# LCDTFT_FPC40P_RGB_FULL.net
KiCad netlist of a schematic drawn in Altium Designer
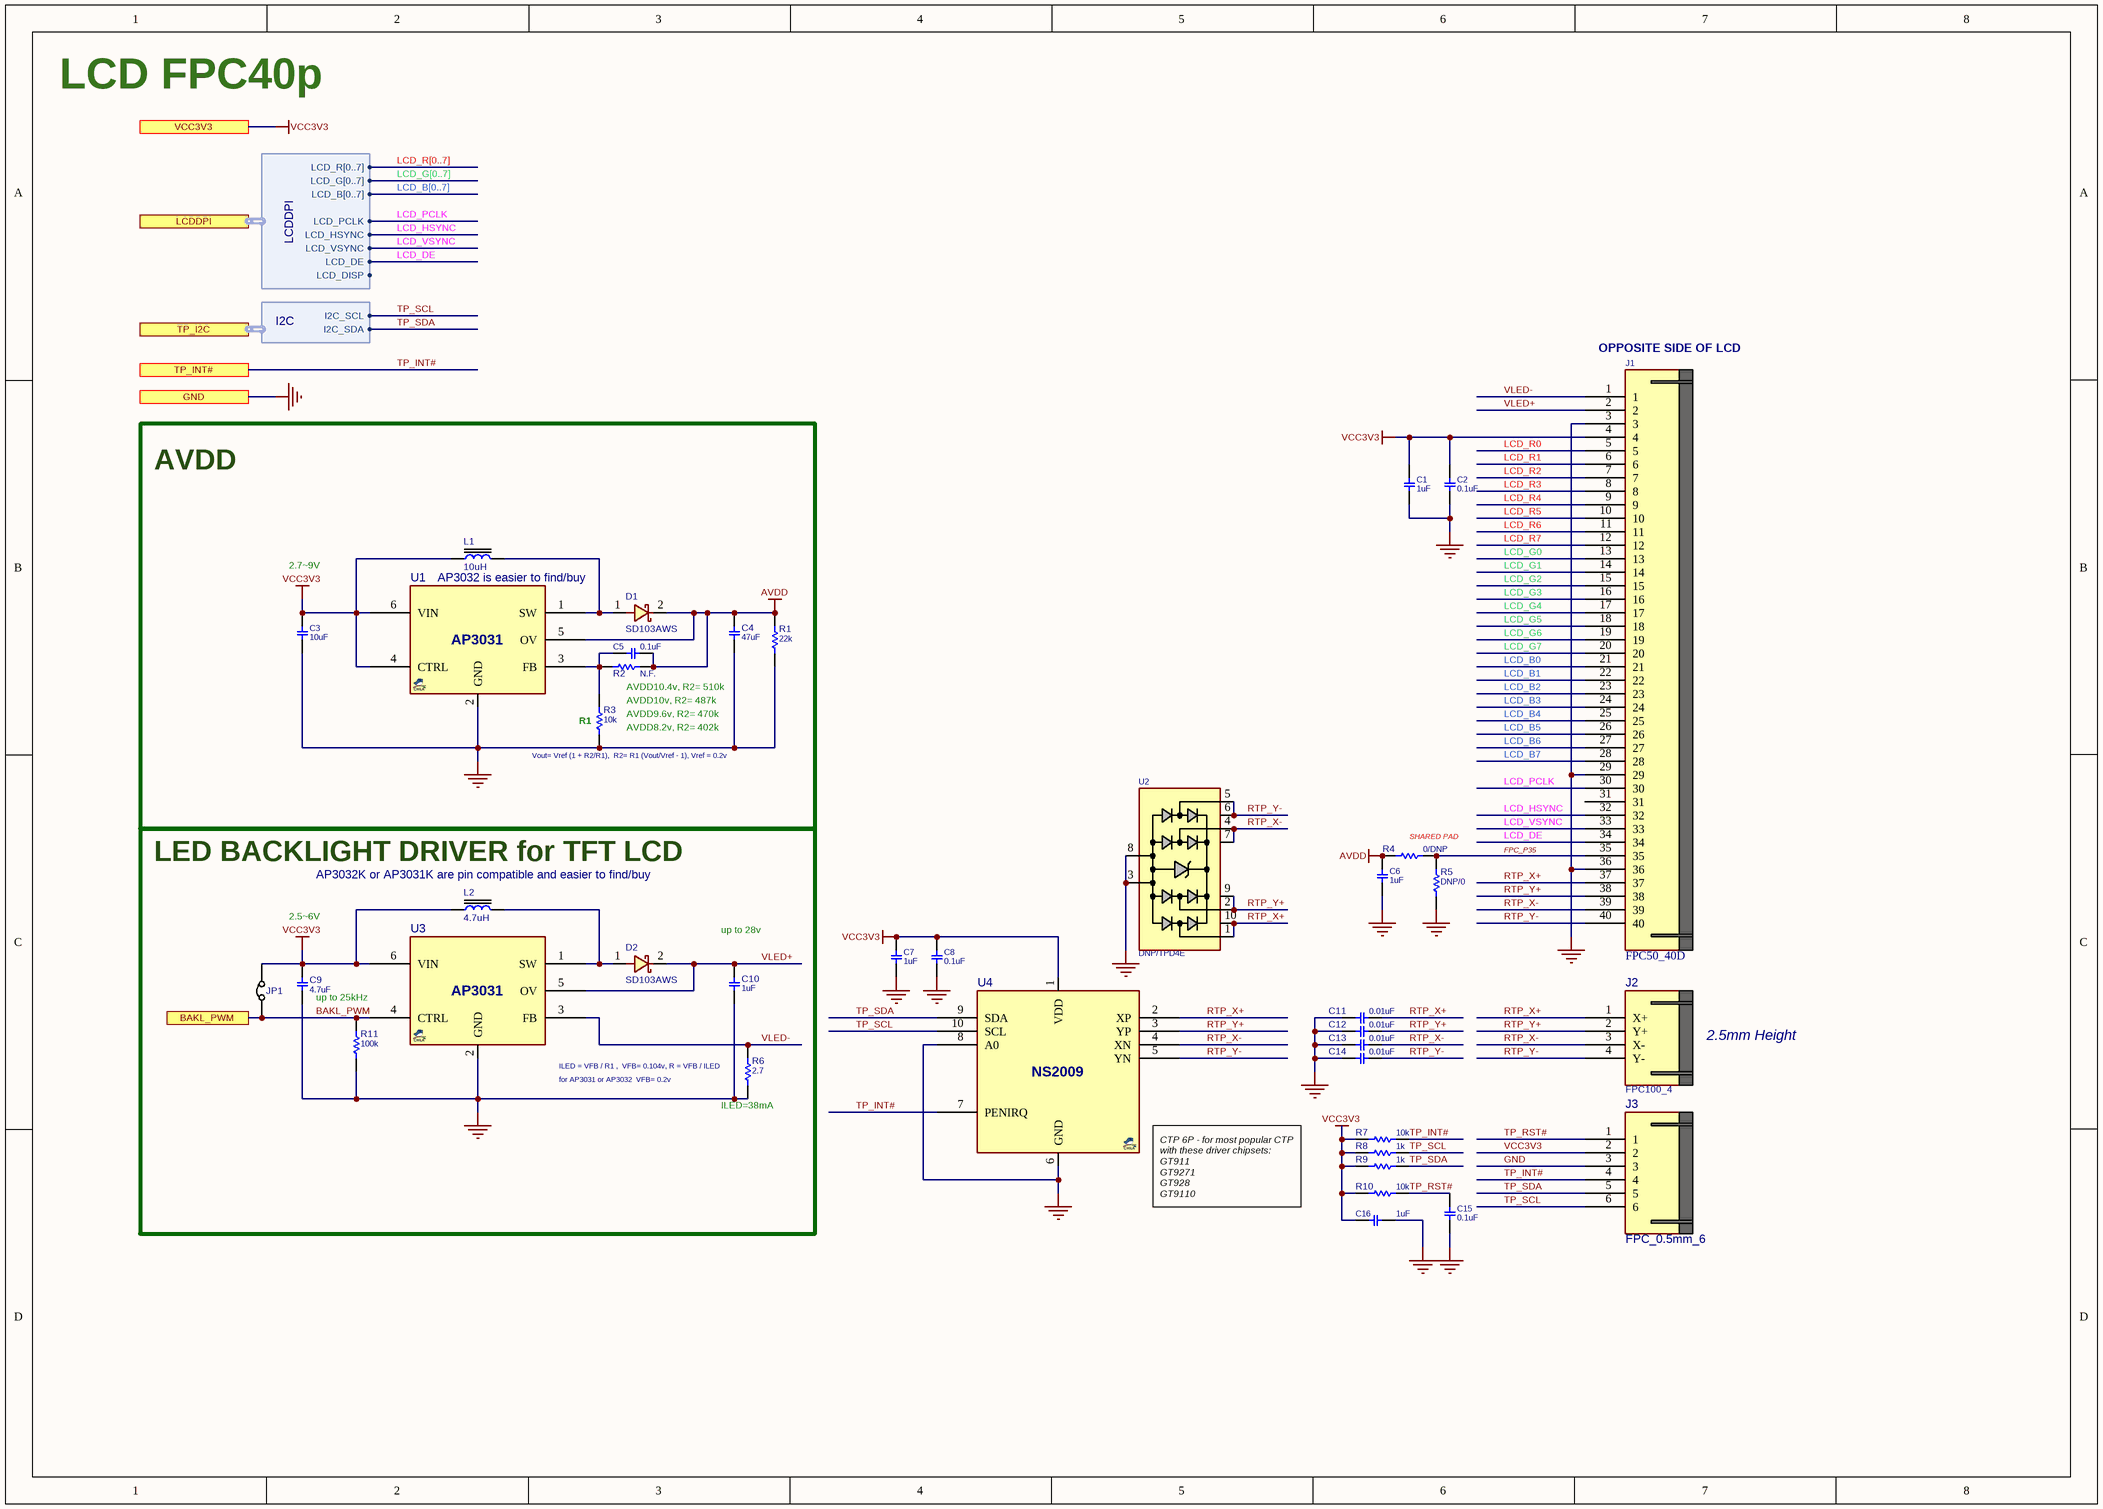
[diagram p0: LCDTFT_FPC40P_RGB_FULL.SchDoc]

(export (version "E")
  (design (tool "Eeschema 10.0.6"))
  (components
    (comp (ref "C1")
      (value "1uF")
      (footprint "C0402")
      (description "CAP, MLCC")
      (fields (field (name "MANF_P#") "CL05A105KO5NNND") (field (name "MANF") "Samsung"))
      (libsource (lib "passive_smd") (part "CAP_SMD_MLCC"))
    )
    (comp (ref "C2")
      (value "0.1uF")
      (footprint "C0402")
      (description "CAP, MLCC")
      (fields (field (name "MANF_P#") "GRM155R71H104KE14D") (field (name "MANF") "Murata"))
      (libsource (lib "passive_smd") (part "CAP_SMD_MLCC"))
    )
    (comp (ref "C3")
      (value "10uF")
      (footprint "C0402")
      (description "CAP, MLCC")
      (fields (field (name "MANF_P#") "CL05A106MP5NUNC") (field (name "MANF") "Samsung"))
      (libsource (lib "passive_smd") (part "CAP_SMD_MLCC"))
    )
    (comp (ref "C4")
      (value "47uF")
      (footprint "C1206")
      (description "CAP, MLCC")
      (fields (field (name "MANF_P#") "GRM31CR61E476ME44L") (field (name "MANF") "Murata"))
      (libsource (lib "passive_smd") (part "CAP_SMD_MLCC"))
    )
    (comp (ref "C5")
      (value "0.1uF")
      (footprint "C0402")
      (description "CAP, MLCC, 100nF, 50V, X7R, 10%, 0402C")
      (fields (field (name "MANF") "Murata") (field (name "MANF_P#") "GCM155R71H104KE02D"))
      (libsource (lib "passive_mlcc_smd") (part "CAP_SMD_MLCC_100n50V"))
    )
    (comp (ref "C6")
      (value "1uF")
      (footprint "C0402")
      (description "CAP, MLCC")
      (fields (field (name "MANF_P#") "CL05A105KO5NNND") (field (name "MANF") "Samsung"))
      (libsource (lib "passive_smd") (part "CAP_SMD_MLCC"))
    )
    (comp (ref "C7")
      (value "1uF")
      (footprint "C0402")
      (description "CAP, MLCC")
      (fields (field (name "MANF_P#") "GMK105ABJ105KV-F") (field (name "MANF") "Taiyo Yuden"))
      (libsource (lib "passive_smd") (part "CAP_SMD_MLCC"))
    )
    (comp (ref "C8")
      (value "0.1uF")
      (footprint "C0402")
      (description "CAP, MLCC")
      (fields (field (name "MANF_P#") "GRM155R71H104KE14D") (field (name "MANF") "Murata"))
      (libsource (lib "passive_smd") (part "CAP_SMD_MLCC"))
    )
    (comp (ref "C9")
      (value "4.7uF")
      (footprint "C0402")
      (description "CAP, MLCC")
      (fields (field (name "MANF_P#") "LMK105BBJ475MVLF") (field (name "MANF") "Taiyo Yuden"))
      (libsource (lib "passive_smd") (part "CAP_SMD_MLCC"))
    )
    (comp (ref "C10")
      (value "1uF")
      (footprint "C0603")
      (description "CAP, MLCC")
      (fields (field (name "MANF_P#") "CL10A105KB8NNNC") (field (name "MANF") "Samsung"))
      (libsource (lib "passive_smd") (part "CAP_SMD_MLCC"))
    )
    (comp (ref "C11")
      (value "0.01uF")
      (footprint "C0402")
      (description "CAP, MLCC")
      (libsource (lib "passive_smd") (part "CAP_SMD_MLCC"))
    )
    (comp (ref "C12")
      (value "0.01uF")
      (footprint "C0402")
      (description "CAP, MLCC")
      (libsource (lib "passive_smd") (part "CAP_SMD_MLCC"))
    )
    (comp (ref "C13")
      (value "0.01uF")
      (footprint "C0402")
      (description "CAP, MLCC")
      (libsource (lib "passive_smd") (part "CAP_SMD_MLCC"))
    )
    (comp (ref "C14")
      (value "0.01uF")
      (footprint "C0402")
      (description "CAP, MLCC")
      (libsource (lib "passive_smd") (part "CAP_SMD_MLCC"))
    )
    (comp (ref "C15")
      (value "0.1uF")
      (footprint "C0402")
      (description "CAP, MLCC")
      (fields (field (name "MANF_P#") "GRM155R71H104KE14D") (field (name "MANF") "Murata"))
      (libsource (lib "passive_smd") (part "CAP_SMD_MLCC"))
    )
    (comp (ref "C16")
      (value "1uF")
      (footprint "C0402")
      (description "CAP, MLCC")
      (fields (field (name "MANF_P#") "CL05A105KO5NNND") (field (name "MANF") "Samsung"))
      (libsource (lib "passive_smd") (part "CAP_SMD_MLCC"))
    )
    (comp (ref "D1")
      (value "SD103AWS")
      (footprint "D_SOD323")
      (description "DIODE, SCHOTTKY, 40V, 2A")
      (fields (field (name "MANF") "DIODES"))
      (libsource (lib "diode") (part "DIODE_SMD_SCHOTTKY_1N5819"))
    )
    (comp (ref "D2")
      (value "SD103AWS")
      (footprint "D_SOD323")
      (description "DIODE, SCHOTTKY, 40V, 2A")
      (fields (field (name "MANF") "DIODES"))
      (libsource (lib "diode") (part "DIODE_SMD_SCHOTTKY_1N5819"))
    )
    (comp (ref "J1")
      (value "FPC50_40D")
      (footprint "FPC50_40D_FFC2B29")
      (description "CONN, FPC, 0.50mm pitch, RightAngle, Dual side Contact")
      (fields (field (name "MANF") "GCT") (field (name "MANF_P#") "FFC2B29-40-G"))
      (libsource (lib "conn_fpc") (part "FPC50_40D_FFC2B29"))
    )
    (comp (ref "J2")
      (value "FPC100_4")
      (footprint "FPC100_4HT")
      (description "LCD Resistive touch, FPC 4pin")
      (libsource (lib "lcdtft") (part "LCD_RTP_FPC4P"))
    )
    (comp (ref "J3")
      (value "FPC_0.5mm_6")
      (footprint "FPC50_6")
      (description "CONN, FPC, 0.50mm pitch, RightAngle, Bot. Contact, Hinge type")
      (fields (field (name "MANF") "FCI") (field (name "MANF_P#") "SFV6R1STBE1HLF"))
      (libsource (lib "conn_fpc") (part "FPC50_6"))
    )
    (comp (ref "JP1")
      (value "JMPSOLDER")
      (footprint "JP_60X100")
      (description "JUMPER, HEADER 2PIN")
      (fields (field (name "MANF") "MANF") (field (name "MANF_P#") "MANF_P#"))
      (libsource (lib "test-tp_jumper") (part "JUMPER_SOLDER"))
    )
    (comp (ref "L1")
      (value "10uH")
      (footprint "L_4")
      (description "INDUCTOR, POWER, SMD")
      (fields (field (name "MANF_P#") "GCD43-100MC"))
      (libsource (lib "passive") (part "INDPWR_SMD"))
    )
    (comp (ref "L2")
      (value "4.7uH")
      (footprint "L1008")
      (description "INDUCTOR, POWER, SMD")
      (fields (field (name "MANF_P#") "TMS252012ALM-4R7MTAA"))
      (libsource (lib "passive") (part "INDPWR_SMD"))
    )
    (comp (ref "R1")
      (value "22k")
      (footprint "R0402")
      (description "RESISTOR, SMD, 20K, 0402")
      (fields (field (name "MANF") "Yageo") (field (name "MANF_P#") "RK73H1ETTP2002F"))
      (libsource (lib "chila_passive") (part "RES_SMD"))
    )
    (comp (ref "R2")
      (value "N.F.")
      (footprint "R0402")
      (description "RESISTOR, SMD, 20K, 0402")
      (fields (field (name "MANF") "Yageo") (field (name "MANF_P#") "RK73H1ETTP2002F"))
      (libsource (lib "chila_passive") (part "RES_SMD"))
    )
    (comp (ref "R3")
      (value "10k")
      (footprint "R0402")
      (description "RESISTOR, SMD, 20K, 0402")
      (fields (field (name "MANF") "Yageo") (field (name "MANF_P#") "RK73H1ETTP2002F"))
      (libsource (lib "chila_passive") (part "RES_SMD"))
    )
    (comp (ref "R4")
      (value "0/DNP")
      (footprint "R0402")
      (description "RESISTOR, SMD")
      (libsource (lib "passive_res_smd") (part "RES_SMD"))
    )
    (comp (ref "R5")
      (value "DNP/0")
      (footprint "R0402")
      (description "RESISTOR, SMD")
      (libsource (lib "passive_res_smd") (part "RES_SMD"))
    )
    (comp (ref "R6")
      (value "2.7")
      (footprint "R0402")
      (description "RESISTOR, SMD, 20K, 0402")
      (fields (field (name "MANF") "Yageo") (field (name "MANF_P#") "RK73H1ETTP2002F"))
      (libsource (lib "chila_passive") (part "RES_SMD"))
    )
    (comp (ref "R7")
      (value "10k")
      (footprint "R0402")
      (description "RESISTOR, SMD")
      (libsource (lib "passive_res_smd") (part "RES_SMD"))
    )
    (comp (ref "R8")
      (value "1k")
      (footprint "R0402")
      (description "RESISTOR, SMD")
      (libsource (lib "passive_res_smd") (part "RES_SMD"))
    )
    (comp (ref "R9")
      (value "1k")
      (footprint "R0402")
      (description "RESISTOR, SMD")
      (libsource (lib "passive_res_smd") (part "RES_SMD"))
    )
    (comp (ref "R10")
      (value "10k")
      (footprint "R0402")
      (description "RESISTOR, SMD")
      (libsource (lib "passive_res_smd") (part "RES_SMD"))
    )
    (comp (ref "R11")
      (value "100k")
      (footprint "R0402")
      (description "RESISTOR, SMD, 20K, 0402")
      (fields (field (name "MANF") "Yageo") (field (name "MANF_P#") "RK73H1ETTP2002F"))
      (libsource (lib "chila_passive") (part "RES_SMD"))
    )
    (comp (ref "U1")
      (value "AP3031")
      (footprint "SOT23_6")
      (description "REG, Switching, Boost, 1.4A, ADJ, 1MHz, SOT-23-6")
      (fields (field (name "MANF_P#") "AP3031K") (field (name "MANF") "Diodes"))
      (libsource (lib "pwr_switching_boost") (part "VREG_AP3031_SOT23"))
    )
    (comp (ref "U2")
      (value "DNP/TPD4E")
      (footprint "SON50_10_2510E")
      (description "TVS, ESD PROTECT, 4CH,")
      (fields (field (name "MANF_P#") "TPD4E05U06DQA") (field (name "MANF") "Texas Instruments"))
      (libsource (lib "protect_tvs_esd_fuse") (part "TVS_X4_TPD4E05U06"))
    )
    (comp (ref "U3")
      (value "AP3031")
      (footprint "SOT23_6")
      (description "REG, Switching, Boost, 1.4A, ADJ, 1MHz, SOT-23-6")
      (fields (field (name "MANF_P#") "AP3031K") (field (name "MANF") "Diodes"))
      (libsource (lib "pwr_switching_boost") (part "VREG_AP3031_SOT23"))
    )
    (comp (ref "U4")
      (value "NS2009")
      (footprint "SOG50_10")
      (description "LCD, Touch Screen Controller, 12Bit, I2C, MSOP-10")
      (fields (field (name "MANF") "NSWAY"))
      (libsource (lib "lcd_resistive_touch_driver") (part "NS2009_MSOP10"))
    )
  )
  (nets
    (net (code "3") (name "/BAKL_PWM") (class "Default")
      (node (ref "JP1") (pin "1") (pinfunction "1_1") (pintype "passive"))
      (node (ref "R11") (pin "1") (pinfunction "1_1") (pintype "passive"))
      (node (ref "U3") (pin "4") (pinfunction "CTRL_4") (pintype "passive"))
    )
    (net (code "4") (name "/FPC_P35") (class "Default")
      (node (ref "J1") (pin "35") (pinfunction "35_35") (pintype "passive"))
      (node (ref "R4") (pin "2") (pinfunction "2_2") (pintype "passive"))
      (node (ref "R5") (pin "1") (pinfunction "1_1") (pintype "passive"))
    )
    (net (code "6") (name "/LCD_B0") (class "Default")
      (node (ref "J1") (pin "21") (pinfunction "21_21") (pintype "passive"))
    )
    (net (code "7") (name "/LCD_B1") (class "Default")
      (node (ref "J1") (pin "22") (pinfunction "22_22") (pintype "passive"))
    )
    (net (code "8") (name "/LCD_B2") (class "Default")
      (node (ref "J1") (pin "23") (pinfunction "23_23") (pintype "passive"))
    )
    (net (code "9") (name "/LCD_B3") (class "Default")
      (node (ref "J1") (pin "24") (pinfunction "24_24") (pintype "passive"))
    )
    (net (code "10") (name "/LCD_B4") (class "Default")
      (node (ref "J1") (pin "25") (pinfunction "25_25") (pintype "passive"))
    )
    (net (code "11") (name "/LCD_B5") (class "Default")
      (node (ref "J1") (pin "26") (pinfunction "26_26") (pintype "passive"))
    )
    (net (code "12") (name "/LCD_B6") (class "Default")
      (node (ref "J1") (pin "27") (pinfunction "27_27") (pintype "passive"))
    )
    (net (code "13") (name "/LCD_B7") (class "Default")
      (node (ref "J1") (pin "28") (pinfunction "28_28") (pintype "passive"))
    )
    (net (code "14") (name "/LCD_DE") (class "Default")
      (node (ref "J1") (pin "34") (pinfunction "34_34") (pintype "passive"))
    )
    (net (code "15") (name "/LCD_G0") (class "Default")
      (node (ref "J1") (pin "13") (pinfunction "13_13") (pintype "passive"))
    )
    (net (code "16") (name "/LCD_G1") (class "Default")
      (node (ref "J1") (pin "14") (pinfunction "14_14") (pintype "passive"))
    )
    (net (code "17") (name "/LCD_G2") (class "Default")
      (node (ref "J1") (pin "15") (pinfunction "15_15") (pintype "passive"))
    )
    (net (code "18") (name "/LCD_G3") (class "Default")
      (node (ref "J1") (pin "16") (pinfunction "16_16") (pintype "passive"))
    )
    (net (code "19") (name "/LCD_G4") (class "Default")
      (node (ref "J1") (pin "17") (pinfunction "17_17") (pintype "passive"))
    )
    (net (code "20") (name "/LCD_G5") (class "Default")
      (node (ref "J1") (pin "18") (pinfunction "18_18") (pintype "passive"))
    )
    (net (code "21") (name "/LCD_G6") (class "Default")
      (node (ref "J1") (pin "19") (pinfunction "19_19") (pintype "passive"))
    )
    (net (code "22") (name "/LCD_G7") (class "Default")
      (node (ref "J1") (pin "20") (pinfunction "20_20") (pintype "passive"))
    )
    (net (code "24") (name "/LCD_HSYNC") (class "Default")
      (node (ref "J1") (pin "32") (pinfunction "32_32") (pintype "passive"))
    )
    (net (code "25") (name "/LCD_PCLK") (class "Default")
      (node (ref "J1") (pin "30") (pinfunction "30_30") (pintype "passive"))
    )
    (net (code "26") (name "/LCD_R0") (class "Default")
      (node (ref "J1") (pin "5") (pinfunction "5_5") (pintype "passive"))
    )
    (net (code "27") (name "/LCD_R1") (class "Default")
      (node (ref "J1") (pin "6") (pinfunction "6_6") (pintype "passive"))
    )
    (net (code "28") (name "/LCD_R2") (class "Default")
      (node (ref "J1") (pin "7") (pinfunction "7_7") (pintype "passive"))
    )
    (net (code "29") (name "/LCD_R3") (class "Default")
      (node (ref "J1") (pin "8") (pinfunction "8_8") (pintype "passive"))
    )
    (net (code "30") (name "/LCD_R4") (class "Default")
      (node (ref "J1") (pin "9") (pinfunction "9_9") (pintype "passive"))
    )
    (net (code "31") (name "/LCD_R5") (class "Default")
      (node (ref "J1") (pin "10") (pinfunction "10_10") (pintype "passive"))
    )
    (net (code "32") (name "/LCD_R6") (class "Default")
      (node (ref "J1") (pin "11") (pinfunction "11_11") (pintype "passive"))
    )
    (net (code "33") (name "/LCD_R7") (class "Default")
      (node (ref "J1") (pin "12") (pinfunction "12_12") (pintype "passive"))
    )
    (net (code "35") (name "/LCD_VSYNC") (class "Default")
      (node (ref "J1") (pin "33") (pinfunction "33_33") (pintype "passive"))
    )
    (net (code "36") (name "/RTP_X+") (class "Default")
      (node (ref "C11") (pin "1") (pinfunction "1_1") (pintype "passive"))
      (node (ref "J1") (pin "37") (pinfunction "37_37") (pintype "passive"))
      (node (ref "J2") (pin "1") (pinfunction "X+_1") (pintype "passive"))
      (node (ref "U2") (pin "1") (pinfunction "1_1") (pintype "passive"))
      (node (ref "U2") (pin "10") (pinfunction "10_10") (pintype "passive"))
      (node (ref "U4") (pin "2") (pinfunction "XP_2") (pintype "passive"))
    )
    (net (code "37") (name "/RTP_X-") (class "Default")
      (node (ref "C13") (pin "1") (pinfunction "1_1") (pintype "passive"))
      (node (ref "J1") (pin "39") (pinfunction "39_39") (pintype "passive"))
      (node (ref "J2") (pin "3") (pinfunction "X-_3") (pintype "passive"))
      (node (ref "U2") (pin "4") (pinfunction "4_4") (pintype "passive"))
      (node (ref "U2") (pin "7") (pinfunction "7_7") (pintype "passive"))
      (node (ref "U4") (pin "4") (pinfunction "XN_4") (pintype "passive"))
    )
    (net (code "38") (name "/RTP_Y+") (class "Default")
      (node (ref "C12") (pin "1") (pinfunction "1_1") (pintype "passive"))
      (node (ref "J1") (pin "38") (pinfunction "38_38") (pintype "passive"))
      (node (ref "J2") (pin "2") (pinfunction "Y+_2") (pintype "passive"))
      (node (ref "U2") (pin "2") (pinfunction "2_2") (pintype "passive"))
      (node (ref "U2") (pin "9") (pinfunction "9_9") (pintype "passive"))
      (node (ref "U4") (pin "3") (pinfunction "YP_3") (pintype "passive"))
    )
    (net (code "39") (name "/RTP_Y-") (class "Default")
      (node (ref "C14") (pin "1") (pinfunction "1_1") (pintype "passive"))
      (node (ref "J1") (pin "40") (pinfunction "40_40") (pintype "passive"))
      (node (ref "J2") (pin "4") (pinfunction "Y-_4") (pintype "passive"))
      (node (ref "U2") (pin "5") (pinfunction "5_5") (pintype "passive"))
      (node (ref "U2") (pin "6") (pinfunction "6_6") (pintype "passive"))
      (node (ref "U4") (pin "5") (pinfunction "YN_5") (pintype "passive"))
    )
    (net (code "40") (name "/TP_INT#") (class "Default")
      (node (ref "J3") (pin "4") (pinfunction "4_4") (pintype "passive"))
      (node (ref "R7") (pin "2") (pinfunction "2_2") (pintype "passive"))
      (node (ref "U4") (pin "7") (pinfunction "PENIRQ_7") (pintype "passive"))
    )
    (net (code "41") (name "/TP_RST#") (class "Default")
      (node (ref "C15") (pin "1") (pinfunction "1_1") (pintype "passive"))
      (node (ref "J3") (pin "1") (pinfunction "1_1") (pintype "passive"))
      (node (ref "R10") (pin "2") (pinfunction "2_2") (pintype "passive"))
    )
    (net (code "42") (name "/TP_SCL") (class "Default")
      (node (ref "J3") (pin "6") (pinfunction "6_6") (pintype "passive"))
      (node (ref "R8") (pin "2") (pinfunction "2_2") (pintype "passive"))
      (node (ref "U4") (pin "10") (pinfunction "SCL_10") (pintype "passive"))
    )
    (net (code "43") (name "/TP_SDA") (class "Default")
      (node (ref "J3") (pin "5") (pinfunction "5_5") (pintype "passive"))
      (node (ref "R9") (pin "2") (pinfunction "2_2") (pintype "passive"))
      (node (ref "U4") (pin "9") (pinfunction "SDA_9") (pintype "passive"))
    )
    (net (code "44") (name "/VLED+") (class "Default")
      (node (ref "C10") (pin "2") (pinfunction "2_2") (pintype "passive"))
      (node (ref "D2") (pin "2") (pinfunction "2_2") (pintype "passive"))
      (node (ref "J1") (pin "2") (pinfunction "2_2") (pintype "passive"))
      (node (ref "U3") (pin "5") (pinfunction "OV_5") (pintype "passive"))
    )
    (net (code "45") (name "/VLED-") (class "Default")
      (node (ref "J1") (pin "1") (pinfunction "1_1") (pintype "passive"))
      (node (ref "R6") (pin "1") (pinfunction "1_1") (pintype "passive"))
      (node (ref "U3") (pin "3") (pinfunction "FB_3") (pintype "passive"))
    )
    (net (code "48") (name "AVDD") (class "Default")
      (node (ref "C4") (pin "2") (pinfunction "2_2") (pintype "passive"))
      (node (ref "C5") (pin "1") (pinfunction "1_1") (pintype "passive"))
      (node (ref "C6") (pin "2") (pinfunction "2_2") (pintype "passive"))
      (node (ref "D1") (pin "2") (pinfunction "2_2") (pintype "passive"))
      (node (ref "R1") (pin "1") (pinfunction "1_1") (pintype "passive"))
      (node (ref "R2") (pin "2") (pinfunction "2_2") (pintype "passive"))
      (node (ref "R4") (pin "1") (pinfunction "1_1") (pintype "passive"))
      (node (ref "U1") (pin "5") (pinfunction "OV_5") (pintype "passive"))
    )
    (net (code "49") (name "GND") (class "Default")
      (node (ref "C1") (pin "2") (pinfunction "2_2") (pintype "passive"))
      (node (ref "C10") (pin "1") (pinfunction "1_1") (pintype "passive"))
      (node (ref "C11") (pin "2") (pinfunction "2_2") (pintype "passive"))
      (node (ref "C12") (pin "2") (pinfunction "2_2") (pintype "passive"))
      (node (ref "C13") (pin "2") (pinfunction "2_2") (pintype "passive"))
      (node (ref "C14") (pin "2") (pinfunction "2_2") (pintype "passive"))
      (node (ref "C15") (pin "2") (pinfunction "2_2") (pintype "passive"))
      (node (ref "C16") (pin "2") (pinfunction "2_2") (pintype "passive"))
      (node (ref "C2") (pin "2") (pinfunction "2_2") (pintype "passive"))
      (node (ref "C3") (pin "1") (pinfunction "1_1") (pintype "passive"))
      (node (ref "C4") (pin "1") (pinfunction "1_1") (pintype "passive"))
      (node (ref "C6") (pin "1") (pinfunction "1_1") (pintype "passive"))
      (node (ref "C7") (pin "2") (pinfunction "2_2") (pintype "passive"))
      (node (ref "C8") (pin "1") (pinfunction "1_1") (pintype "passive"))
      (node (ref "C9") (pin "2") (pinfunction "2_2") (pintype "passive"))
      (node (ref "J1") (pin "29") (pinfunction "29_29") (pintype "passive"))
      (node (ref "J1") (pin "3") (pinfunction "3_3") (pintype "passive"))
      (node (ref "J1") (pin "36") (pinfunction "36_36") (pintype "passive"))
      (node (ref "J3") (pin "3") (pinfunction "3_3") (pintype "passive"))
      (node (ref "R1") (pin "2") (pinfunction "2_2") (pintype "passive"))
      (node (ref "R11") (pin "2") (pinfunction "2_2") (pintype "passive"))
      (node (ref "R3") (pin "2") (pinfunction "2_2") (pintype "passive"))
      (node (ref "R5") (pin "2") (pinfunction "2_2") (pintype "passive"))
      (node (ref "R6") (pin "2") (pinfunction "2_2") (pintype "passive"))
      (node (ref "U1") (pin "2") (pinfunction "GND_2") (pintype "tri_state"))
      (node (ref "U2") (pin "3") (pinfunction "3_3") (pintype "passive"))
      (node (ref "U2") (pin "8") (pinfunction "8_8") (pintype "passive"))
      (node (ref "U3") (pin "2") (pinfunction "GND_2") (pintype "tri_state"))
      (node (ref "U4") (pin "6") (pinfunction "GND_6") (pintype "passive"))
      (node (ref "U4") (pin "8") (pinfunction "A0_8") (pintype "passive"))
    )
    (net (code "50") (name "Net-(U1-FB)") (class "Default")
      (node (ref "C5") (pin "2") (pinfunction "2_2") (pintype "passive"))
      (node (ref "R2") (pin "1") (pinfunction "1_1") (pintype "passive"))
      (node (ref "R3") (pin "1") (pinfunction "1_1") (pintype "passive"))
      (node (ref "U1") (pin "3") (pinfunction "FB_3") (pintype "passive"))
    )
    (net (code "51") (name "Net-(U1-SW)") (class "Default")
      (node (ref "D1") (pin "1") (pinfunction "1_1") (pintype "passive"))
      (node (ref "L1") (pin "2") (pinfunction "2_2") (pintype "passive"))
      (node (ref "U1") (pin "1") (pinfunction "SW_1") (pintype "passive"))
    )
    (net (code "52") (name "Net-(U3-SW)") (class "Default")
      (node (ref "D2") (pin "1") (pinfunction "1_1") (pintype "passive"))
      (node (ref "L2") (pin "2") (pinfunction "2_2") (pintype "passive"))
      (node (ref "U3") (pin "1") (pinfunction "SW_1") (pintype "passive"))
    )
    (net (code "53") (name "VCC3V3") (class "Default")
      (node (ref "C1") (pin "1") (pinfunction "1_1") (pintype "passive"))
      (node (ref "C16") (pin "1") (pinfunction "1_1") (pintype "passive"))
      (node (ref "C2") (pin "1") (pinfunction "1_1") (pintype "passive"))
      (node (ref "C3") (pin "2") (pinfunction "2_2") (pintype "passive"))
      (node (ref "C7") (pin "1") (pinfunction "1_1") (pintype "passive"))
      (node (ref "C8") (pin "2") (pinfunction "2_2") (pintype "passive"))
      (node (ref "C9") (pin "1") (pinfunction "1_1") (pintype "passive"))
      (node (ref "J1") (pin "4") (pinfunction "4_4") (pintype "passive"))
      (node (ref "J3") (pin "2") (pinfunction "2_2") (pintype "passive"))
      (node (ref "JP1") (pin "2") (pinfunction "2_2") (pintype "passive"))
      (node (ref "L1") (pin "1") (pinfunction "1_1") (pintype "passive"))
      (node (ref "L2") (pin "1") (pinfunction "1_1") (pintype "passive"))
      (node (ref "R10") (pin "1") (pinfunction "1_1") (pintype "passive"))
      (node (ref "R7") (pin "1") (pinfunction "1_1") (pintype "passive"))
      (node (ref "R8") (pin "1") (pinfunction "1_1") (pintype "passive"))
      (node (ref "R9") (pin "1") (pinfunction "1_1") (pintype "passive"))
      (node (ref "U1") (pin "4") (pinfunction "CTRL_4") (pintype "passive"))
      (node (ref "U1") (pin "6") (pinfunction "VIN_6") (pintype "passive"))
      (node (ref "U3") (pin "6") (pinfunction "VIN_6") (pintype "passive"))
      (node (ref "U4") (pin "1") (pinfunction "VDD_1") (pintype "passive"))
    )
    (net (code "54") (name "unconnected-(J1-Pad31)") (class "Default")
      (node (ref "J1") (pin "31") (pinfunction "31_31") (pintype "passive"))
    )
  )
)
